# Safety.net
KiCad netlist of a schematic drawn in Altium Designer
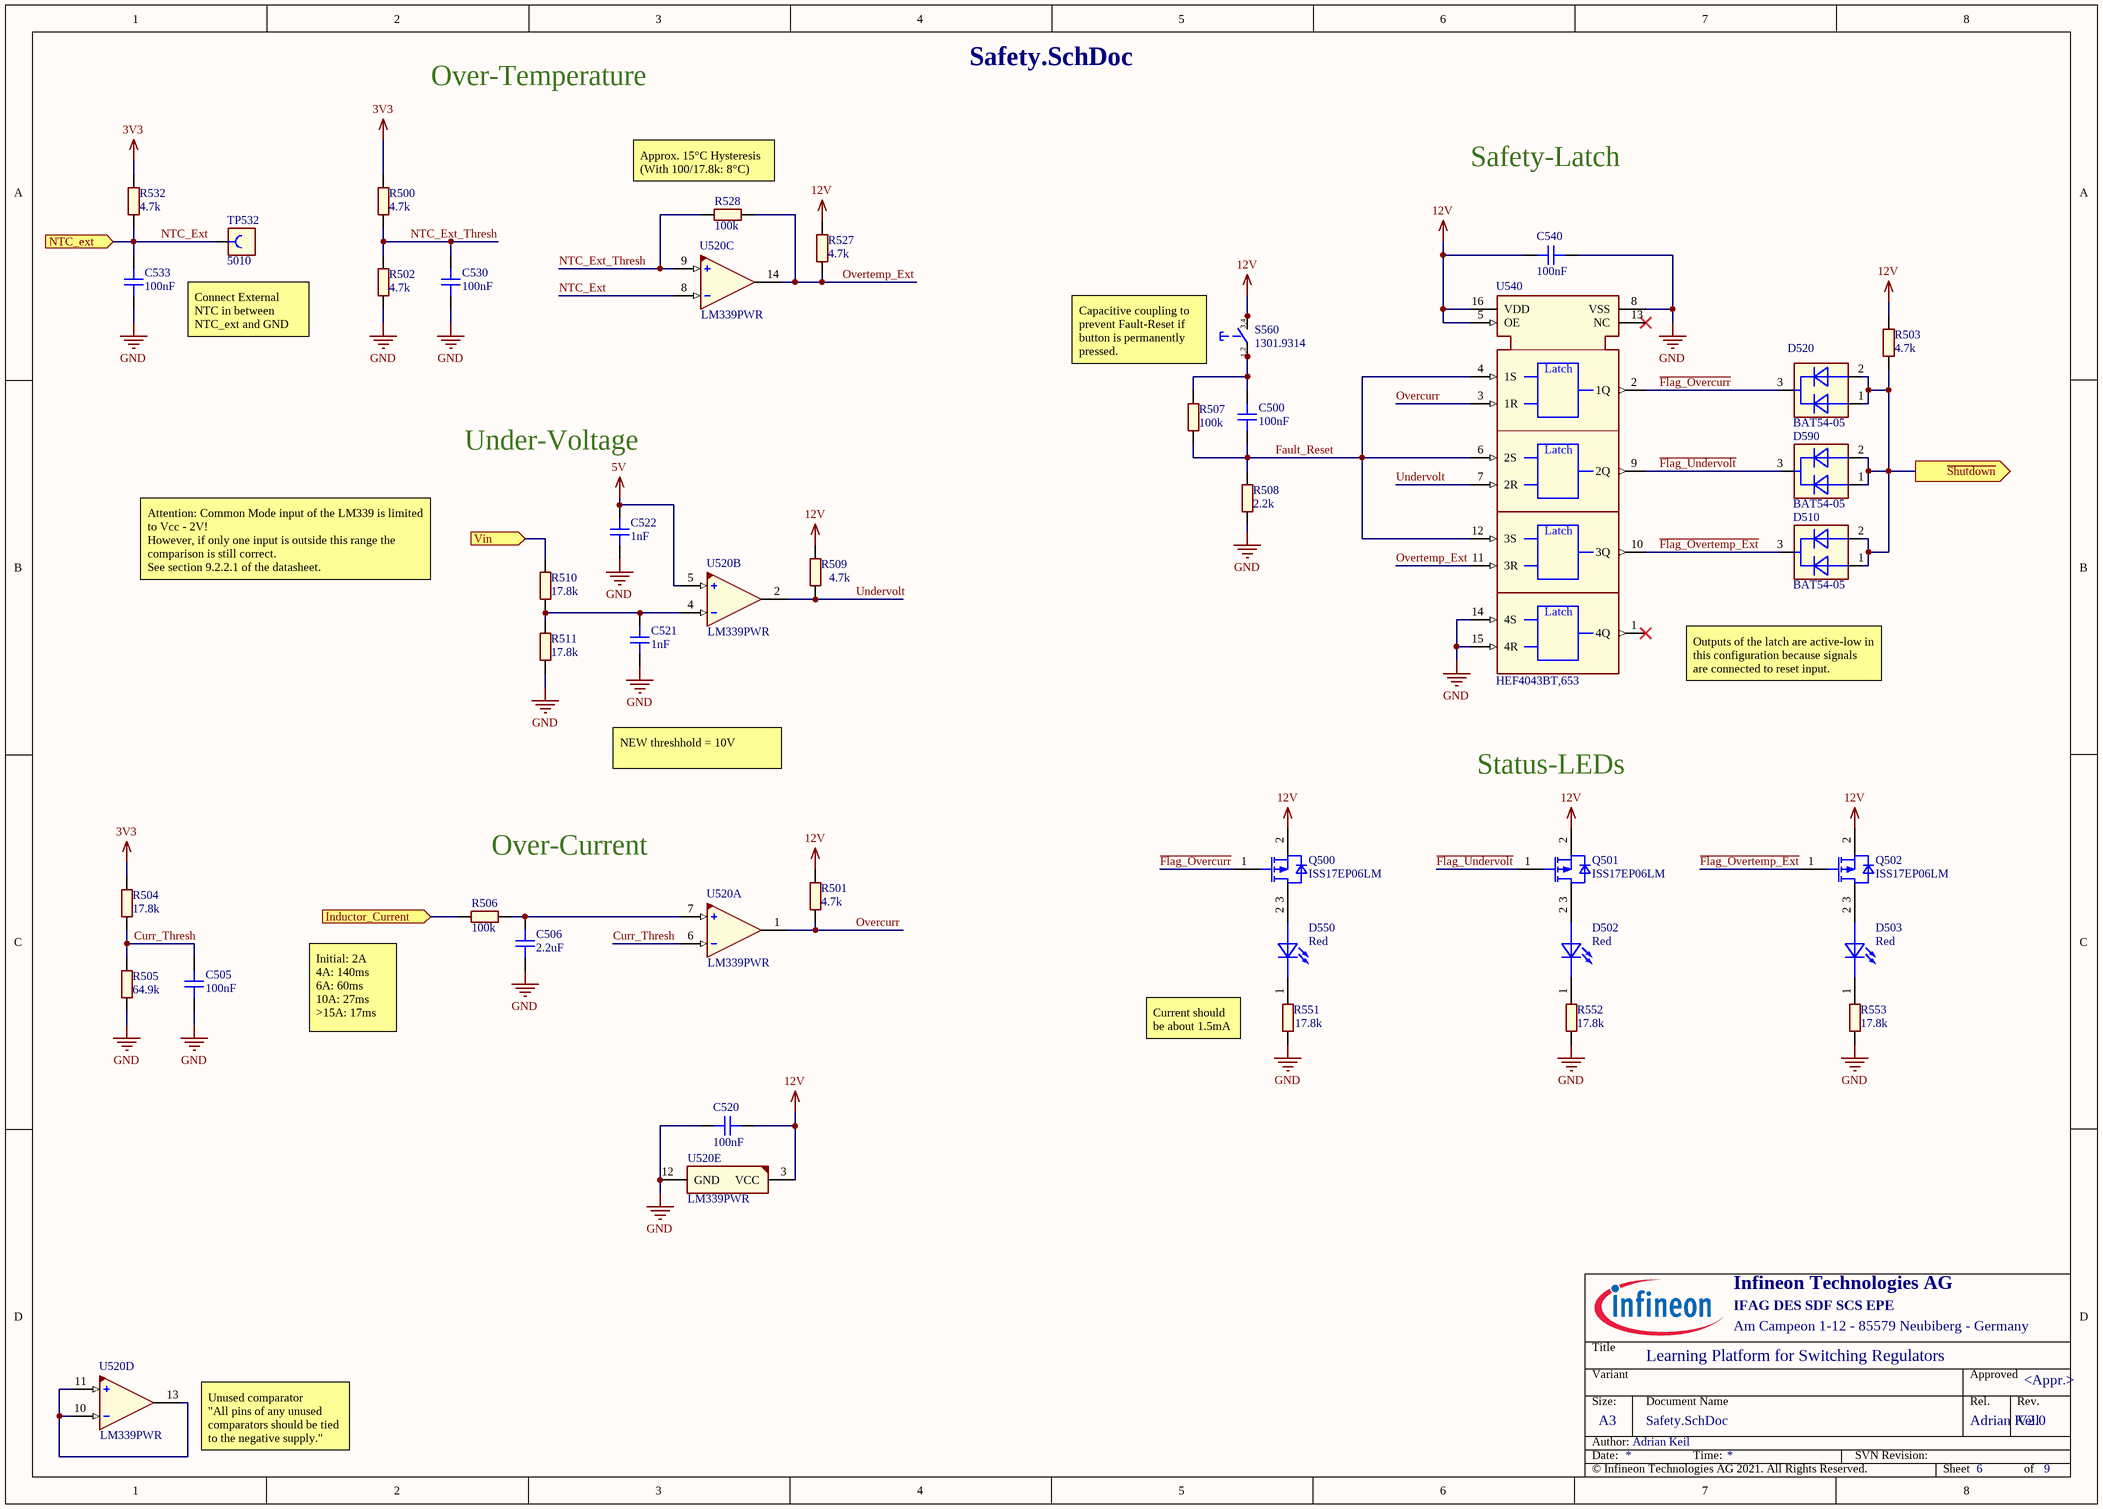
[diagram p0: Safety.SchDoc]

(export (version "E")
  (design (tool "Eeschema 10.0.6"))
  (components
    (comp (ref "C500")
      (value "100nF")
      (footprint "CAPC1608X90N-2")
      (description "CAP / CERA / 100nF / 50V / 10% / X7R (EIA) / -55°C to 125°C / 0603 / SMD / -")
      (fields (field (name "MANUFACTURER") "AVX"))
      (libsource (lib "PCBLibraryData") (part "CAP-SGL-STD-02P_00000001"))
    )
    (comp (ref "C505")
      (value "100nF")
      (footprint "CAPC1608X90N-2")
      (description "CAP / CERA / 100nF / 50V / 10% / X7R (EIA) / -55°C to 125°C / 0603 / SMD / -")
      (fields (field (name "MANUFACTURER") "AVX"))
      (libsource (lib "PCBLibraryData") (part "CAP-SGL-STD-02P_00000001"))
    )
    (comp (ref "C506")
      (value "2.2uF")
      (footprint "CAPC1608X90N-3")
      (description "CAP / CERA / 2.2uF / 25V / 10% / X5R (EIA) / -55°C to 85°C / 0603(1608) / SMD / -")
      (fields (field (name "LEGACY PARTNUMBER") "CAP01010924") (field (name "MANUFACTURER") "MuRata"))
      (libsource (lib "PCBLibraryData") (part "CAP-SGL-STD-02P_00000001"))
    )
    (comp (ref "C520")
      (value "100nF")
      (footprint "CAPC1608X90N-2")
      (description "CAP / CERA / 100nF / 50V / 10% / X7R (EIA) / -55°C to 125°C / 0603 / SMD / -")
      (fields (field (name "MANUFACTURER") "AVX"))
      (libsource (lib "PCBLibraryData") (part "CAP-SGL-STD-02P_00000001"))
    )
    (comp (ref "C521")
      (value "1nF")
      (footprint "CAPC1608X87N-1")
      (description "CAP / CERA / 1nF / 50V / 10% / X7R (EIA) / -55°C to 125°C / 0603 (1608) / SMD / -")
      (fields (field (name "MANUFACTURER") "Wurth Elektronik"))
      (libsource (lib "PCBLibraryData") (part "CAP-SGL-STD-02P_00000001"))
    )
    (comp (ref "C522")
      (value "1nF")
      (footprint "CAPC1608X87N-1")
      (description "CAP / CERA / 1nF / 50V / 10% / X7R (EIA) / -55°C to 125°C / 0603 (1608) / SMD / -")
      (fields (field (name "MANUFACTURER") "Wurth Elektronik"))
      (libsource (lib "PCBLibraryData") (part "CAP-SGL-STD-02P_00000001"))
    )
    (comp (ref "C530")
      (value "100nF")
      (footprint "CAPC1608X90N-2")
      (description "CAP / CERA / 100nF / 50V / 10% / X7R (EIA) / -55°C to 125°C / 0603 / SMD / -")
      (fields (field (name "MANUFACTURER") "AVX"))
      (libsource (lib "PCBLibraryData") (part "CAP-SGL-STD-02P_00000001"))
    )
    (comp (ref "C533")
      (value "100nF")
      (footprint "CAPC1608X90N-2")
      (description "CAP / CERA / 100nF / 50V / 10% / X7R (EIA) / -55°C to 125°C / 0603 / SMD / -")
      (fields (field (name "MANUFACTURER") "AVX"))
      (libsource (lib "PCBLibraryData") (part "CAP-SGL-STD-02P_00000001"))
    )
    (comp (ref "C540")
      (value "100nF")
      (footprint "CAPC1608X90N-2")
      (description "CAP / CERA / 100nF / 50V / 10% / X7R (EIA) / -55°C to 125°C / 0603 / SMD / -")
      (fields (field (name "MANUFACTURER") "AVX"))
      (libsource (lib "PCBLibraryData") (part "CAP-SGL-STD-02P_00000001"))
    )
    (comp (ref "D502")
      (value "Red")
      (footprint "LEDSC160X80X80-2N-1")
      (description "WL-SMCW SMT Mono-color Chip LED Waterclear, Red,630nm")
      (fields (field (name "MANUFACTURER") "Wurth Elektronik"))
      (libsource (lib "PCBLibraryData") (part "d_led_a"))
    )
    (comp (ref "D503")
      (value "Red")
      (footprint "LEDSC160X80X80-2N-1")
      (description "WL-SMCW SMT Mono-color Chip LED Waterclear, Red,630nm")
      (fields (field (name "MANUFACTURER") "Wurth Elektronik"))
      (libsource (lib "PCBLibraryData") (part "d_led_a"))
    )
    (comp (ref "D510")
      (value "BAT54-05")
      (footprint "SOT95P240X110-3N-1-V")
      (description "Silicon Schottky Diode, LS(nH) 1.8, VR 30V")
      (fields
        (field (name "LEGACY PARTNUMBER") "IFX01401370")
        (field (name "MANUFACTURER") "Infineon Technologies")
      )
      (libsource (lib "PCBLibraryData") (part "d_dual_a1a2c3_3p"))
    )
    (comp (ref "D520")
      (value "BAT54-05")
      (footprint "SOT95P240X110-3N-1-V")
      (description "Silicon Schottky Diode, LS(nH) 1.8, VR 30V")
      (fields
        (field (name "LEGACY PARTNUMBER") "IFX01401370")
        (field (name "MANUFACTURER") "Infineon Technologies")
      )
      (libsource (lib "PCBLibraryData") (part "d_dual_a1a2c3_3p"))
    )
    (comp (ref "D550")
      (value "Red")
      (footprint "LEDSC160X80X80-2N-1")
      (description "WL-SMCW SMT Mono-color Chip LED Waterclear, Red,630nm")
      (fields (field (name "MANUFACTURER") "Wurth Elektronik"))
      (libsource (lib "PCBLibraryData") (part "d_led_a"))
    )
    (comp (ref "D590")
      (value "BAT54-05")
      (footprint "SOT95P240X110-3N-1-V")
      (description "Silicon Schottky Diode, LS(nH) 1.8, VR 30V")
      (fields
        (field (name "LEGACY PARTNUMBER") "IFX01401370")
        (field (name "MANUFACTURER") "Infineon Technologies")
      )
      (libsource (lib "PCBLibraryData") (part "d_dual_a1a2c3_3p"))
    )
    (comp (ref "Q500")
      (value "ISS17EP06LM")
      (footprint "SOT95P240X110-3N-1-V")
      (description "OptiMOSTM Small Signal Transistor, -60 V")
      (fields (field (name "MANUFACTURER") "Infineon Technologies"))
      (libsource (lib "PCBLibraryData") (part "igfet_p_ch_enh_dio_1g2s3d_3p"))
    )
    (comp (ref "Q501")
      (value "ISS17EP06LM")
      (footprint "SOT95P240X110-3N-1-V")
      (description "OptiMOSTM Small Signal Transistor, -60 V")
      (fields (field (name "MANUFACTURER") "Infineon Technologies"))
      (libsource (lib "PCBLibraryData") (part "igfet_p_ch_enh_dio_1g2s3d_3p"))
    )
    (comp (ref "Q502")
      (value "ISS17EP06LM")
      (footprint "SOT95P240X110-3N-1-V")
      (description "OptiMOSTM Small Signal Transistor, -60 V")
      (fields (field (name "MANUFACTURER") "Infineon Technologies"))
      (libsource (lib "PCBLibraryData") (part "igfet_p_ch_enh_dio_1g2s3d_3p"))
    )
    (comp (ref "R500")
      (value "4.7k")
      (footprint "RESC1609X55N")
      (description "RES / STD / 4.7k / 100mW / 1% / 100ppm/K / -55°C to 155°C / 1.60mm L X 0.85mm W X 0.55mm H / - / -")
      (fields (field (name "MANUFACTURER") "Panasonic"))
      (libsource (lib "PCBLibraryData") (part "RES-SGL-STD-02P_00000006"))
    )
    (comp (ref "R501")
      (value "4.7k")
      (footprint "RESC1609X55N")
      (description "RES / STD / 4.7k / 100mW / 1% / 100ppm/K / -55°C to 155°C / 1.60mm L X 0.85mm W X 0.55mm H / - / -")
      (fields (field (name "MANUFACTURER") "Panasonic"))
      (libsource (lib "PCBLibraryData") (part "RES-SGL-STD-02P_00000006"))
    )
    (comp (ref "R502")
      (value "4.7k")
      (footprint "RESC1609X55N")
      (description "RES / STD / 4.7k / 100mW / 1% / 100ppm/K / -55°C to 155°C / 1.60mm L X 0.85mm W X 0.55mm H / - / -")
      (fields (field (name "MANUFACTURER") "Panasonic"))
      (libsource (lib "PCBLibraryData") (part "RES-SGL-STD-02P_00000006"))
    )
    (comp (ref "R503")
      (value "4.7k")
      (footprint "RESC1609X55N")
      (description "RES / STD / 4.7k / 100mW / 1% / 100ppm/K / -55°C to 155°C / 1.60mm L X 0.85mm W X 0.55mm H / - / -")
      (fields (field (name "MANUFACTURER") "Panasonic"))
      (libsource (lib "PCBLibraryData") (part "RES-SGL-STD-02P_00000006"))
    )
    (comp (ref "R504")
      (value "17.8k")
      (footprint "RESC1608X60N")
      (fields (field (name "MANUFACTURER") "Multicomp"))
      (libsource (lib "PCBLibraryData") (part "RES-SGL-STD-02P_00000006"))
    )
    (comp (ref "R505")
      (value "64.9k")
      (footprint "RESC1608X60N")
      (fields (field (name "MANUFACTURER") "Multicomp"))
      (libsource (lib "PCBLibraryData") (part "RES-SGL-STD-02P_00000006"))
    )
    (comp (ref "R506")
      (value "100k")
      (footprint "RESC1508X60N")
      (fields (field (name "MANUFACTURER") "Bourns"))
      (libsource (lib "") (part "RES-SGL-STD-02P_00000006_3"))
    )
    (comp (ref "R507")
      (value "100k")
      (footprint "RESC1508X60N")
      (fields (field (name "MANUFACTURER") "Bourns"))
      (libsource (lib "PCBLibraryData") (part "RES-SGL-STD-02P_00000006"))
    )
    (comp (ref "R508")
      (value "2.2k")
      (footprint "RESC1609X50N")
      (description "RES / STD / 2.2k / 100mW / 1% / 100ppm/K / -55°C to 155°C / 0603 / SMD / -")
      (fields (field (name "LEGACY PARTNUMBER") "RES01801179") (field (name "MANUFACTURER") "Vishay"))
      (libsource (lib "") (part "RES-SGL-STD-02P_00000006_1"))
    )
    (comp (ref "R509")
      (value "4.7k")
      (footprint "RESC1609X55N")
      (description "RES / STD / 4.7k / 100mW / 1% / 100ppm/K / -55°C to 155°C / 1.60mm L X 0.85mm W X 0.55mm H / - / -")
      (fields (field (name "MANUFACTURER") "Panasonic"))
      (libsource (lib "PCBLibraryData") (part "RES-SGL-STD-02P_00000006"))
    )
    (comp (ref "R510")
      (value "17.8k")
      (footprint "RESC1608X60N")
      (fields (field (name "MANUFACTURER") "Multicomp"))
      (libsource (lib "") (part "RES-SGL-STD-02P_00000006_1"))
    )
    (comp (ref "R511")
      (value "17.8k")
      (footprint "RESC1608X60N")
      (fields (field (name "MANUFACTURER") "Multicomp"))
      (libsource (lib "PCBLibraryData") (part "RES-SGL-STD-02P_00000006"))
    )
    (comp (ref "R527")
      (value "4.7k")
      (footprint "RESC1609X55N")
      (description "RES / STD / 4.7k / 100mW / 1% / 100ppm/K / -55°C to 155°C / 1.60mm L X 0.85mm W X 0.55mm H / - / -")
      (fields (field (name "MANUFACTURER") "Panasonic"))
      (libsource (lib "PCBLibraryData") (part "RES-SGL-STD-02P_00000006"))
    )
    (comp (ref "R528")
      (value "100k")
      (footprint "RESC1609X50N")
      (description "RES / STD / 100k / 100mW / 1% / 100ppm/K / -55°C to 155°C / 0603 / SMD / -")
      (fields (field (name "LEGACY PARTNUMBER") "RES01801371") (field (name "MANUFACTURER") "Vishay"))
      (libsource (lib "") (part "RES-SGL-STD-02P_00000006_2"))
    )
    (comp (ref "R532")
      (value "4.7k")
      (footprint "RESC1609X55N")
      (description "RES / STD / 4.7k / 100mW / 1% / 100ppm/K / -55°C to 155°C / 1.60mm L X 0.85mm W X 0.55mm H / - / -")
      (fields (field (name "MANUFACTURER") "Panasonic"))
      (libsource (lib "PCBLibraryData") (part "RES-SGL-STD-02P_00000006"))
    )
    (comp (ref "R551")
      (value "17.8k")
      (footprint "RESC1608X60N")
      (fields (field (name "MANUFACTURER") "Multicomp"))
      (libsource (lib "") (part "RES-SGL-STD-02P_00000006_1"))
    )
    (comp (ref "R552")
      (value "17.8k")
      (footprint "RESC1608X60N")
      (fields (field (name "MANUFACTURER") "Multicomp"))
      (libsource (lib "PCBLibraryData") (part "RES-SGL-STD-02P_00000006"))
    )
    (comp (ref "R553")
      (value "17.8k")
      (footprint "RESC1608X60N")
      (fields (field (name "MANUFACTURER") "Multicomp"))
      (libsource (lib "PCBLibraryData") (part "RES-SGL-STD-02P_00000006"))
    )
    (comp (ref "S560")
      (value "1301.9314")
      (footprint "SW-SMD-1301.9314")
      (description "Pushbutton Tactile Switch, Single Pole Single Throw, 4 Pins")
      (fields (field (name "LEGACY PARTNUMBER") "CON01500305") (field (name "MANUFACTURER") "Schurter"))
      (libsource (lib "PCBLibraryData") (part "sw_sr_no12_34_4p"))
    )
    (comp (ref "TP532")
      (value "5010")
      (footprint "CON-THT-TP-5010")
      (description "PC Test Point-Multipurpose THT, Red")
      (fields
        (field (name "LEGACY PARTNUMBER") "CON01500529")
        (field (name "MANUFACTURER") "Keystone Electronics Corp.")
      )
      (libsource (lib "PCBLibraryData") (part "connector_1_f"))
    )
    (comp (ref "U520")
      (value "LM339PWR")
      (footprint "SOP65P640X120-14N-1")
      (description "Quad Differential Comparator")
      (fields
        (field (name "LEGACY PARTNUMBER") "IC02600564")
        (field (name "MANUFACTURER") "Texas Instruments")
      )
      (libsource (lib "PCBLibraryData") (part "LM339PWR"))
    )
    (comp (ref "U540")
      (value "HEF4043BT,653")
      (footprint "SOIC127P600X175-16N-6")
      (description "Quad R/S latch with 3-state outputs")
      (fields (field (name "MANUFACTURER") "Nexperia"))
      (libsource (lib "PCBLibraryData") (part "HEF4043B"))
    )
  )
  (nets
    (net (code "1") (name "/Curr_Thresh") (class "Default")
      (node (ref "C505") (pin "2") (pinfunction "2_2") (pintype "passive"))
      (node (ref "R504") (pin "1") (pinfunction "1_1") (pintype "passive"))
      (node (ref "R505") (pin "2") (pinfunction "2_2") (pintype "passive"))
      (node (ref "U520") (pin "6") (pinfunction "1IN_N_6") (pintype "input"))
    )
    (net (code "2") (name "/Fault_Reset") (class "Default")
      (node (ref "C500") (pin "2") (pinfunction "2_2") (pintype "passive"))
      (node (ref "R507") (pin "1") (pinfunction "1_1") (pintype "passive"))
      (node (ref "R508") (pin "1") (pinfunction "1_1") (pintype "passive"))
      (node (ref "U540") (pin "12") (pinfunction "3S_12") (pintype "input"))
      (node (ref "U540") (pin "4") (pinfunction "1S_4") (pintype "input"))
      (node (ref "U540") (pin "6") (pinfunction "2S_6") (pintype "input"))
    )
    (net (code "3") (name "/Flag_Overcurr") (class "Default")
      (node (ref "D520") (pin "3") (pinfunction "CATHODE_3") (pintype "passive"))
      (node (ref "Q500") (pin "1") (pinfunction "GATE_1") (pintype "passive"))
      (node (ref "U540") (pin "2") (pinfunction "1Q_2") (pintype "output"))
    )
    (net (code "4") (name "/Flag_Overtemp_Ext") (class "Default")
      (node (ref "D510") (pin "3") (pinfunction "CATHODE_3") (pintype "passive"))
      (node (ref "Q502") (pin "1") (pinfunction "GATE_1") (pintype "passive"))
      (node (ref "U540") (pin "10") (pinfunction "3Q_10") (pintype "output"))
    )
    (net (code "5") (name "/Flag_Undervolt") (class "Default")
      (node (ref "D590") (pin "3") (pinfunction "CATHODE_3") (pintype "passive"))
      (node (ref "Q501") (pin "1") (pinfunction "GATE_1") (pintype "passive"))
      (node (ref "U540") (pin "9") (pinfunction "2Q_9") (pintype "output"))
    )
    (net (code "6") (name "/Inductor_Current") (class "Default")
      (node (ref "R506") (pin "1") (pinfunction "1_1") (pintype "passive"))
    )
    (net (code "7") (name "/NTC_Ext") (class "Default")
      (node (ref "C533") (pin "2") (pinfunction "2_2") (pintype "passive"))
      (node (ref "R532") (pin "1") (pinfunction "1_1") (pintype "passive"))
      (node (ref "TP532") (pin "1") (pinfunction "1_1") (pintype "passive"))
      (node (ref "U520") (pin "8") (pinfunction "3IN_N_8") (pintype "input"))
    )
    (net (code "8") (name "/NTC_Ext_Thresh") (class "Default")
      (node (ref "C530") (pin "2") (pinfunction "2_2") (pintype "passive"))
      (node (ref "R500") (pin "1") (pinfunction "1_1") (pintype "passive"))
      (node (ref "R502") (pin "2") (pinfunction "2_2") (pintype "passive"))
      (node (ref "R528") (pin "2") (pinfunction "2_2") (pintype "passive"))
      (node (ref "U520") (pin "9") (pinfunction "3IN_P_9") (pintype "input"))
    )
    (net (code "9") (name "/Overcurr") (class "Default")
      (node (ref "R501") (pin "1") (pinfunction "1_1") (pintype "passive"))
      (node (ref "U520") (pin "1") (pinfunction "1OUT_1") (pintype "open_collector"))
      (node (ref "U540") (pin "3") (pinfunction "1R_3") (pintype "input"))
    )
    (net (code "10") (name "/Overtemp_Ext") (class "Default")
      (node (ref "R527") (pin "1") (pinfunction "1_1") (pintype "passive"))
      (node (ref "R528") (pin "1") (pinfunction "1_1") (pintype "passive"))
      (node (ref "U520") (pin "14") (pinfunction "3OUT_14") (pintype "open_collector"))
      (node (ref "U540") (pin "11") (pinfunction "3R_11") (pintype "input"))
    )
    (net (code "11") (name "/Shutdown") (class "Default")
      (node (ref "D510") (pin "1") (pinfunction "ANODE_1_1") (pintype "passive"))
      (node (ref "D510") (pin "2") (pinfunction "ANODE_2_2") (pintype "passive"))
      (node (ref "D520") (pin "1") (pinfunction "ANODE_1_1") (pintype "passive"))
      (node (ref "D520") (pin "2") (pinfunction "ANODE_2_2") (pintype "passive"))
      (node (ref "D590") (pin "1") (pinfunction "ANODE_1_1") (pintype "passive"))
      (node (ref "D590") (pin "2") (pinfunction "ANODE_2_2") (pintype "passive"))
      (node (ref "R503") (pin "1") (pinfunction "1_1") (pintype "passive"))
    )
    (net (code "12") (name "/Undervolt") (class "Default")
      (node (ref "R509") (pin "1") (pinfunction "1_1") (pintype "passive"))
      (node (ref "U520") (pin "2") (pinfunction "2OUT_2") (pintype "open_collector"))
      (node (ref "U540") (pin "7") (pinfunction "2R_7") (pintype "input"))
    )
    (net (code "13") (name "/Vin") (class "Default")
      (node (ref "R510") (pin "1") (pinfunction "1_1") (pintype "passive"))
    )
    (net (code "14") (name "3V3") (class "Default")
      (node (ref "R500") (pin "2") (pinfunction "2_2") (pintype "passive"))
      (node (ref "R504") (pin "2") (pinfunction "2_2") (pintype "passive"))
      (node (ref "R532") (pin "2") (pinfunction "2_2") (pintype "passive"))
    )
    (net (code "15") (name "5V") (class "Default")
      (node (ref "C522") (pin "2") (pinfunction "2_2") (pintype "passive"))
      (node (ref "U520") (pin "5") (pinfunction "2IN_P_5") (pintype "input"))
    )
    (net (code "16") (name "12V") (class "Default")
      (node (ref "C520") (pin "1") (pinfunction "1_1") (pintype "passive"))
      (node (ref "C540") (pin "2") (pinfunction "2_2") (pintype "passive"))
      (node (ref "Q500") (pin "2") (pinfunction "SOURCE_2") (pintype "passive"))
      (node (ref "Q501") (pin "2") (pinfunction "SOURCE_2") (pintype "passive"))
      (node (ref "Q502") (pin "2") (pinfunction "SOURCE_2") (pintype "passive"))
      (node (ref "R501") (pin "2") (pinfunction "2_2") (pintype "passive"))
      (node (ref "R503") (pin "2") (pinfunction "2_2") (pintype "passive"))
      (node (ref "R509") (pin "2") (pinfunction "2_2") (pintype "passive"))
      (node (ref "R527") (pin "2") (pinfunction "2_2") (pintype "passive"))
      (node (ref "S560") (pin "3") (pinfunction "3_3") (pintype "passive"))
      (node (ref "S560") (pin "4") (pinfunction "4_4") (pintype "passive"))
      (node (ref "U520") (pin "3") (pinfunction "VCC_3") (pintype "power_in"))
      (node (ref "U540") (pin "16") (pinfunction "VDD_16") (pintype "power_in"))
      (node (ref "U540") (pin "5") (pinfunction "OE_5") (pintype "input"))
    )
    (net (code "17") (name "GND") (class "Default")
      (node (ref "C505") (pin "1") (pinfunction "1_1") (pintype "passive"))
      (node (ref "C506") (pin "1") (pinfunction "1_1") (pintype "passive"))
      (node (ref "C520") (pin "2") (pinfunction "2_2") (pintype "passive"))
      (node (ref "C521") (pin "1") (pinfunction "1_1") (pintype "passive"))
      (node (ref "C522") (pin "1") (pinfunction "1_1") (pintype "passive"))
      (node (ref "C530") (pin "1") (pinfunction "1_1") (pintype "passive"))
      (node (ref "C533") (pin "1") (pinfunction "1_1") (pintype "passive"))
      (node (ref "C540") (pin "1") (pinfunction "1_1") (pintype "passive"))
      (node (ref "R502") (pin "1") (pinfunction "1_1") (pintype "passive"))
      (node (ref "R505") (pin "1") (pinfunction "1_1") (pintype "passive"))
      (node (ref "R508") (pin "2") (pinfunction "2_2") (pintype "passive"))
      (node (ref "R511") (pin "1") (pinfunction "1_1") (pintype "passive"))
      (node (ref "R551") (pin "2") (pinfunction "2_2") (pintype "passive"))
      (node (ref "R552") (pin "1") (pinfunction "1_1") (pintype "passive"))
      (node (ref "R553") (pin "1") (pinfunction "1_1") (pintype "passive"))
      (node (ref "U520") (pin "12") (pinfunction "GND_12") (pintype "power_in"))
      (node (ref "U540") (pin "14") (pinfunction "4S_14") (pintype "input"))
      (node (ref "U540") (pin "15") (pinfunction "4R_15") (pintype "input"))
      (node (ref "U540") (pin "8") (pinfunction "VSS_8") (pintype "power_in"))
    )
    (net (code "18") (name "Net-(C500-Pad1)") (class "Default")
      (node (ref "C500") (pin "1") (pinfunction "1_1") (pintype "passive"))
      (node (ref "R507") (pin "2") (pinfunction "2_2") (pintype "passive"))
      (node (ref "S560") (pin "1") (pinfunction "1_1") (pintype "passive"))
      (node (ref "S560") (pin "2") (pinfunction "2_2") (pintype "passive"))
    )
    (net (code "19") (name "Net-(D502-Anode)") (class "Default")
      (node (ref "D502") (pin "2") (pinfunction "Anode_2") (pintype "passive"))
      (node (ref "Q501") (pin "3") (pinfunction "DRAIN_3") (pintype "passive"))
    )
    (net (code "20") (name "Net-(D502-Cathode)") (class "Default")
      (node (ref "D502") (pin "1") (pinfunction "Cathode_1") (pintype "passive"))
      (node (ref "R552") (pin "2") (pinfunction "2_2") (pintype "passive"))
    )
    (net (code "21") (name "Net-(D503-Anode)") (class "Default")
      (node (ref "D503") (pin "2") (pinfunction "Anode_2") (pintype "passive"))
      (node (ref "Q502") (pin "3") (pinfunction "DRAIN_3") (pintype "passive"))
    )
    (net (code "22") (name "Net-(D503-Cathode)") (class "Default")
      (node (ref "D503") (pin "1") (pinfunction "Cathode_1") (pintype "passive"))
      (node (ref "R553") (pin "2") (pinfunction "2_2") (pintype "passive"))
    )
    (net (code "23") (name "Net-(D550-Anode)") (class "Default")
      (node (ref "D550") (pin "2") (pinfunction "Anode_2") (pintype "passive"))
      (node (ref "Q500") (pin "3") (pinfunction "DRAIN_3") (pintype "passive"))
    )
    (net (code "24") (name "Net-(D550-Cathode)") (class "Default")
      (node (ref "D550") (pin "1") (pinfunction "Cathode_1") (pintype "passive"))
      (node (ref "R551") (pin "1") (pinfunction "1_1") (pintype "passive"))
    )
    (net (code "25") (name "Net-(U520A-1IN_P)") (class "Default")
      (node (ref "C506") (pin "2") (pinfunction "2_2") (pintype "passive"))
      (node (ref "R506") (pin "2") (pinfunction "2_2") (pintype "passive"))
      (node (ref "U520") (pin "7") (pinfunction "1IN_P_7") (pintype "input"))
    )
    (net (code "26") (name "Net-(U520B-2IN_N)") (class "Default")
      (node (ref "C521") (pin "2") (pinfunction "2_2") (pintype "passive"))
      (node (ref "R510") (pin "2") (pinfunction "2_2") (pintype "passive"))
      (node (ref "R511") (pin "2") (pinfunction "2_2") (pintype "passive"))
      (node (ref "U520") (pin "4") (pinfunction "2IN_N_4") (pintype "input"))
    )
    (net (code "27") (name "Net-(U520D-4IN_N)") (class "Default")
      (node (ref "U520") (pin "10") (pinfunction "4IN_N_10") (pintype "input"))
      (node (ref "U520") (pin "11") (pinfunction "4IN_P_11") (pintype "input"))
      (node (ref "U520") (pin "13") (pinfunction "4OUT_13") (pintype "open_collector"))
    )
    (net (code "28") (name "unconnected-(U540-4Q-Pad1)") (class "Default")
      (node (ref "U540") (pin "1") (pinfunction "4Q_1") (pintype "output+no_connect"))
    )
    (net (code "29") (name "unconnected-(U540-NC-Pad13)") (class "Default")
      (node (ref "U540") (pin "13") (pinfunction "NC_13") (pintype "passive+no_connect"))
    )
  )
)
